# nrf24multipro.net
KiCad netlist of a schematic drawn in EAGLE
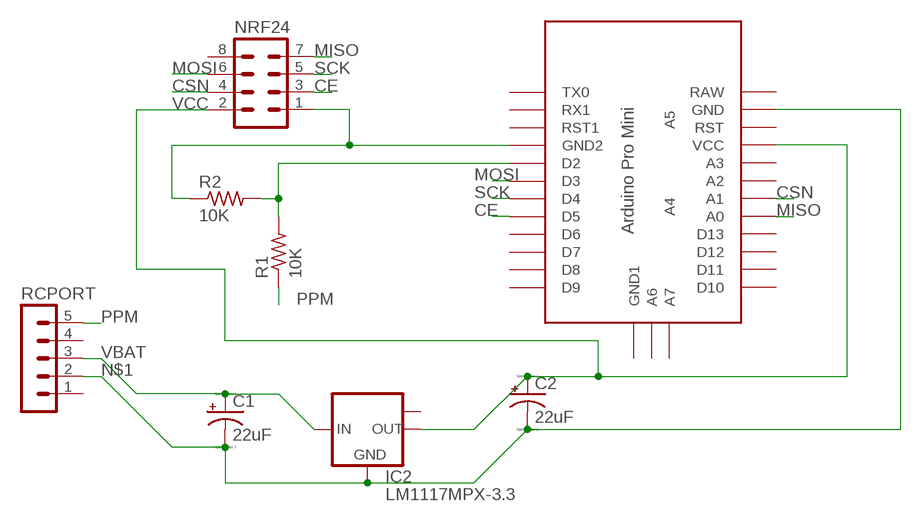
[diagram p0: schematic, sheet 1]

(export (version "E")
  (design (tool "Eeschema 10.0.6"))
  (components
    (comp (ref "C1")
      (value "22uF")
      (footprint "eagle-import:E1,8-4")
      (libsource (lib "eagle-import") (part "CPOL-USE1.8-4"))
    )
    (comp (ref "C2")
      (value "22uF")
      (footprint "eagle-import:E1,8-4")
      (libsource (lib "eagle-import") (part "CPOL-USE1.8-4"))
    )
    (comp (ref "IC2")
      (value "LM1117MPX-3.3")
      (footprint "eagle-import:SOT223")
      (libsource (lib "eagle-import") (part "LM1117MPX-3.3"))
    )
    (comp (ref "NRF24")
      (value "MA04-2")
      (footprint "eagle-import:MA04-2")
      (libsource (lib "eagle-import") (part "MA04-2"))
    )
    (comp (ref "R1")
      (value "10K")
      (footprint "eagle-import:0207_10")
      (libsource (lib "eagle-import") (part "R-US_0207/10"))
    )
    (comp (ref "R2")
      (value "10K")
      (footprint "eagle-import:0207_10")
      (libsource (lib "eagle-import") (part "R-US_0207/10"))
    )
    (comp (ref "RCPORT")
      (value "MA05-1")
      (footprint "eagle-import:MA05-1")
      (libsource (lib "eagle-import") (part "MA05-1"))
    )
    (comp (ref "U$1")
      (value "ABK-PRO-MINI")
      (footprint "eagle-import:ABK-PRO-MINI")
      (libsource (lib "eagle-import") (part "ABK-PRO-MINI"))
    )
  )
  (nets
    (net (code "1") (name "/CE") (class "Default")
      (node (ref "NRF24") (pin "3") (pinfunction "3_3") (pintype "passive"))
      (node (ref "U$1") (pin "D5") (pinfunction "D5_D5") (pintype "bidirectional"))
    )
    (net (code "2") (name "/CSN") (class "Default")
      (node (ref "NRF24") (pin "4") (pinfunction "4_4") (pintype "passive"))
      (node (ref "U$1") (pin "A1") (pinfunction "A1_A1") (pintype "bidirectional"))
    )
    (net (code "3") (name "/MISO") (class "Default")
      (node (ref "NRF24") (pin "7") (pinfunction "7_7") (pintype "passive"))
      (node (ref "U$1") (pin "A0") (pinfunction "A0_A0") (pintype "bidirectional"))
    )
    (net (code "4") (name "/MOSI") (class "Default")
      (node (ref "NRF24") (pin "6") (pinfunction "6_6") (pintype "passive"))
      (node (ref "U$1") (pin "D3") (pinfunction "D3_D3") (pintype "bidirectional"))
    )
    (net (code "5") (name "/N$1") (class "Default")
      (node (ref "C1") (pin "-") (pinfunction "-_-") (pintype "passive"))
      (node (ref "C2") (pin "-") (pinfunction "-_-") (pintype "passive"))
      (node (ref "IC2") (pin "1") (pinfunction "GND_1") (pintype "input"))
      (node (ref "RCPORT") (pin "2") (pinfunction "2_2") (pintype "passive"))
      (node (ref "U$1") (pin "GND") (pinfunction "GND_GND") (pintype "bidirectional"))
    )
    (net (code "6") (name "/PPM") (class "Default")
      (node (ref "R1") (pin "1") (pinfunction "1_1") (pintype "passive"))
      (node (ref "RCPORT") (pin "5") (pinfunction "5_5") (pintype "passive"))
    )
    (net (code "7") (name "/SCK") (class "Default")
      (node (ref "NRF24") (pin "5") (pinfunction "5_5") (pintype "passive"))
      (node (ref "U$1") (pin "D4") (pinfunction "D4_D4") (pintype "bidirectional"))
    )
    (net (code "8") (name "/VBAT") (class "Default")
      (node (ref "C1") (pin "+") (pinfunction "+_+") (pintype "passive"))
      (node (ref "IC2") (pin "3") (pinfunction "IN_3") (pintype "input"))
      (node (ref "RCPORT") (pin "3") (pinfunction "3_3") (pintype "passive"))
    )
    (net (code "9") (name "/VCC") (class "Default")
      (node (ref "C2") (pin "+") (pinfunction "+_+") (pintype "passive"))
      (node (ref "IC2") (pin "2") (pinfunction "OUT_2") (pintype "passive"))
      (node (ref "NRF24") (pin "2") (pinfunction "2_2") (pintype "passive"))
      (node (ref "U$1") (pin "VCC") (pinfunction "VCC_VCC") (pintype "bidirectional"))
    )
    (net (code "10") (name "Net-(R1-Pad2)") (class "Default")
      (node (ref "R1") (pin "2") (pinfunction "2_2") (pintype "passive"))
      (node (ref "R2") (pin "2") (pinfunction "2_2") (pintype "passive"))
      (node (ref "U$1") (pin "D2") (pinfunction "D2_D2") (pintype "bidirectional"))
    )
    (net (code "11") (name "Net-(U$1-GND2)") (class "Default")
      (node (ref "NRF24") (pin "1") (pinfunction "1_1") (pintype "passive"))
      (node (ref "R2") (pin "1") (pinfunction "1_1") (pintype "passive"))
      (node (ref "U$1") (pin "GND1") (pinfunction "GND2_GND1") (pintype "bidirectional"))
    )
    (net (code "12") (name "unconnected-(IC2-OUT1-PadTAB)") (class "Default")
      (node (ref "IC2") (pin "TAB") (pinfunction "OUT1_TAB") (pintype "passive"))
    )
    (net (code "13") (name "unconnected-(NRF24-Pad8)") (class "Default")
      (node (ref "NRF24") (pin "8") (pinfunction "8_8") (pintype "passive"))
    )
    (net (code "14") (name "unconnected-(RCPORT-Pad1)") (class "Default")
      (node (ref "RCPORT") (pin "1") (pinfunction "1_1") (pintype "passive"))
    )
    (net (code "15") (name "unconnected-(RCPORT-Pad4)") (class "Default")
      (node (ref "RCPORT") (pin "4") (pinfunction "4_4") (pintype "passive"))
    )
    (net (code "16") (name "unconnected-(U$1-GND1-PadGND4)") (class "Default")
      (node (ref "U$1") (pin "GND4") (pinfunction "GND1_GND4") (pintype "bidirectional"))
    )
    (net (code "17") (name "unconnected-(U$1-PadA2)") (class "Default")
      (node (ref "U$1") (pin "A2") (pinfunction "A2_A2") (pintype "bidirectional"))
    )
    (net (code "18") (name "unconnected-(U$1-PadA3)") (class "Default")
      (node (ref "U$1") (pin "A3") (pinfunction "A3_A3") (pintype "bidirectional"))
    )
    (net (code "19") (name "unconnected-(U$1-PadA4)") (class "Default")
      (node (ref "U$1") (pin "A4") (pinfunction "A4_A4") (pintype "bidirectional"))
    )
    (net (code "20") (name "unconnected-(U$1-PadA5)") (class "Default")
      (node (ref "U$1") (pin "A5") (pinfunction "A5_A5") (pintype "bidirectional"))
    )
    (net (code "21") (name "unconnected-(U$1-PadA6)") (class "Default")
      (node (ref "U$1") (pin "A6") (pinfunction "A6_A6") (pintype "bidirectional"))
    )
    (net (code "22") (name "unconnected-(U$1-PadA7)") (class "Default")
      (node (ref "U$1") (pin "A7") (pinfunction "A7_A7") (pintype "bidirectional"))
    )
    (net (code "23") (name "unconnected-(U$1-PadD6)") (class "Default")
      (node (ref "U$1") (pin "D6") (pinfunction "D6_D6") (pintype "bidirectional"))
    )
    (net (code "24") (name "unconnected-(U$1-PadD7)") (class "Default")
      (node (ref "U$1") (pin "D7") (pinfunction "D7_D7") (pintype "bidirectional"))
    )
    (net (code "25") (name "unconnected-(U$1-PadD8)") (class "Default")
      (node (ref "U$1") (pin "D8") (pinfunction "D8_D8") (pintype "bidirectional"))
    )
    (net (code "26") (name "unconnected-(U$1-PadD9)") (class "Default")
      (node (ref "U$1") (pin "D9") (pinfunction "D9_D9") (pintype "bidirectional"))
    )
    (net (code "27") (name "unconnected-(U$1-PadD10)") (class "Default")
      (node (ref "U$1") (pin "D10") (pinfunction "D10_D10") (pintype "bidirectional"))
    )
    (net (code "28") (name "unconnected-(U$1-PadD11)") (class "Default")
      (node (ref "U$1") (pin "D11") (pinfunction "D11_D11") (pintype "bidirectional"))
    )
    (net (code "29") (name "unconnected-(U$1-PadD12)") (class "Default")
      (node (ref "U$1") (pin "D12") (pinfunction "D12_D12") (pintype "bidirectional"))
    )
    (net (code "30") (name "unconnected-(U$1-PadD13)") (class "Default")
      (node (ref "U$1") (pin "D13") (pinfunction "D13_D13") (pintype "bidirectional"))
    )
    (net (code "31") (name "unconnected-(U$1-PadRAW)") (class "Default")
      (node (ref "U$1") (pin "RAW") (pinfunction "RAW_RAW") (pintype "bidirectional"))
    )
    (net (code "32") (name "unconnected-(U$1-PadRST)") (class "Default")
      (node (ref "U$1") (pin "RST") (pinfunction "RST_RST") (pintype "bidirectional"))
    )
    (net (code "33") (name "unconnected-(U$1-PadRST1)") (class "Default")
      (node (ref "U$1") (pin "RST1") (pinfunction "RST1_RST1") (pintype "bidirectional"))
    )
    (net (code "34") (name "unconnected-(U$1-PadRX1)") (class "Default")
      (node (ref "U$1") (pin "RX1") (pinfunction "RX1_RX1") (pintype "bidirectional"))
    )
    (net (code "35") (name "unconnected-(U$1-PadTX0)") (class "Default")
      (node (ref "U$1") (pin "TX0") (pinfunction "TX0_TX0") (pintype "bidirectional"))
    )
  )
)
